# PCIe_x1_edge.net
KiCad netlist of a schematic drawn in Altium Designer
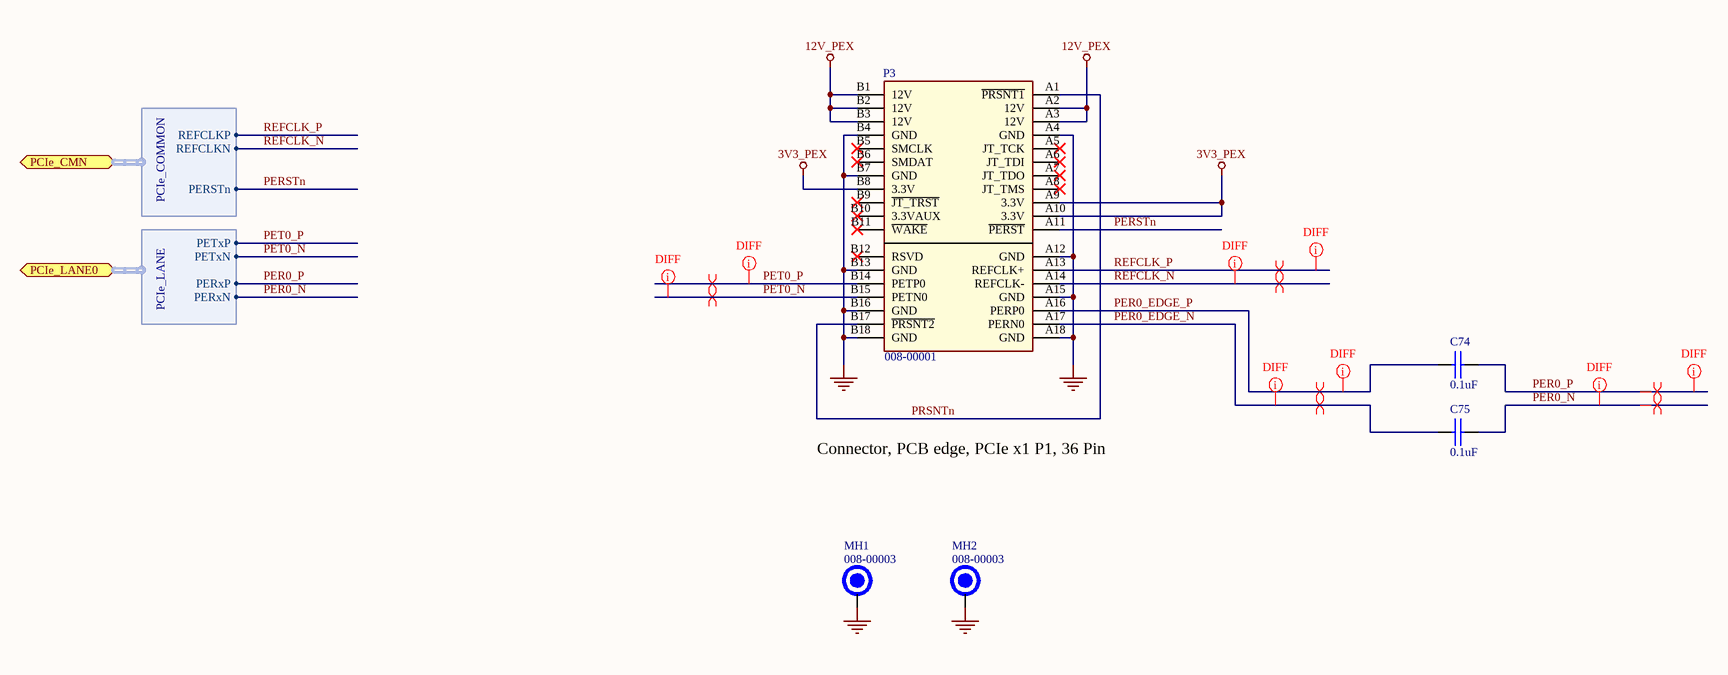
[diagram p0: PCIe_x1_edge.SchDoc]

(export (version "E")
  (design (tool "Eeschema 10.0.6"))
  (components
    (comp (ref "C74")
      (value "0.1uF")
      (footprint "005-00008")
      (description "Capacitor 0.1uF 16V 10% 0402 X7R")
      (fields (field (name "PART NUMBER") "011-00011") (field (name "VOLTAGE") "16V"))
      (libsource (lib "CES Component Library") (part "004-00003"))
    )
    (comp (ref "C75")
      (value "0.1uF")
      (footprint "005-00008")
      (description "Capacitor 0.1uF 16V 10% 0402 X7R")
      (fields (field (name "PART NUMBER") "011-00011") (field (name "VOLTAGE") "16V"))
      (libsource (lib "CES Component Library") (part "004-00003"))
    )
    (comp (ref "MH1")
      (value "004-00017")
      (footprint "005-00019")
      (description "PCB Mounting Hole, Round Pad, 250mil Diameter, 125mil Drill")
      (fields (field (name "PART NUMBER") "008-00003"))
      (libsource (lib "CES Component Library") (part "004-00017"))
    )
    (comp (ref "MH2")
      (value "004-00017")
      (footprint "005-00019")
      (description "PCB Mounting Hole, Round Pad, 250mil Diameter, 125mil Drill")
      (fields (field (name "PART NUMBER") "008-00003"))
      (libsource (lib "CES Component Library") (part "004-00017"))
    )
    (comp (ref "P3")
      (value "004-00018")
      (footprint "005-00020")
      (description "Connector, PCB edge, PCIe x1 P1, 36 Pin")
      (fields (field (name "PART NUMBER") "008-00001"))
      (libsource (lib "CES Component Library") (part "004-00018"))
    )
  )
  (nets
    (net (code "3") (name "/PER0_EDGE_N") (class "Default")
      (node (ref "C75") (pin "1") (pinfunction "1_1") (pintype "passive"))
      (node (ref "P3") (pin "A17") (pinfunction "PERN0_A17") (pintype "passive"))
    )
    (net (code "4") (name "/PER0_EDGE_P") (class "Default")
      (node (ref "C74") (pin "1") (pinfunction "1_1") (pintype "passive"))
      (node (ref "P3") (pin "A16") (pinfunction "PERP0_A16") (pintype "passive"))
    )
    (net (code "5") (name "/PER0_N") (class "Default")
      (node (ref "C75") (pin "2") (pinfunction "2_2") (pintype "passive"))
    )
    (net (code "6") (name "/PER0_P") (class "Default")
      (node (ref "C74") (pin "2") (pinfunction "2_2") (pintype "passive"))
    )
    (net (code "7") (name "/PERSTn") (class "Default")
      (node (ref "P3") (pin "A11") (pinfunction "~{PERST}_A11") (pintype "passive"))
    )
    (net (code "8") (name "/PET0_N") (class "Default")
      (node (ref "P3") (pin "B15") (pinfunction "PETN0_B15") (pintype "passive"))
    )
    (net (code "9") (name "/PET0_P") (class "Default")
      (node (ref "P3") (pin "B14") (pinfunction "PETP0_B14") (pintype "passive"))
    )
    (net (code "10") (name "/PRSNTn") (class "Default")
      (node (ref "P3") (pin "A1") (pinfunction "~{PRSNT1}_A1") (pintype "passive"))
      (node (ref "P3") (pin "B17") (pinfunction "~{PRSNT2}_B17") (pintype "passive"))
    )
    (net (code "11") (name "/REFCLK_N") (class "Default")
      (node (ref "P3") (pin "A14") (pinfunction "REFCLK-_A14") (pintype "passive"))
    )
    (net (code "12") (name "/REFCLK_P") (class "Default")
      (node (ref "P3") (pin "A13") (pinfunction "REFCLK+_A13") (pintype "passive"))
    )
    (net (code "15") (name "3V3_PEX") (class "Default")
      (node (ref "P3") (pin "A10") (pinfunction "3.3V_A10") (pintype "passive"))
      (node (ref "P3") (pin "A9") (pinfunction "3.3V_A9") (pintype "passive"))
      (node (ref "P3") (pin "B8") (pinfunction "3.3V_B8") (pintype "passive"))
    )
    (net (code "16") (name "12V_PEX") (class "Default")
      (node (ref "P3") (pin "A2") (pinfunction "12V_A2") (pintype "passive"))
      (node (ref "P3") (pin "A3") (pinfunction "12V_A3") (pintype "passive"))
      (node (ref "P3") (pin "B1") (pinfunction "12V_B1") (pintype "passive"))
      (node (ref "P3") (pin "B2") (pinfunction "12V_B2") (pintype "passive"))
      (node (ref "P3") (pin "B3") (pinfunction "12V_B3") (pintype "passive"))
    )
    (net (code "17") (name "GND") (class "Default")
      (node (ref "MH1") (pin "1") (pinfunction "1_1") (pintype "passive"))
      (node (ref "MH2") (pin "1") (pinfunction "1_1") (pintype "passive"))
      (node (ref "P3") (pin "A12") (pinfunction "GND_A12") (pintype "passive"))
      (node (ref "P3") (pin "A15") (pinfunction "GND_A15") (pintype "passive"))
      (node (ref "P3") (pin "A18") (pinfunction "GND_A18") (pintype "passive"))
      (node (ref "P3") (pin "A4") (pinfunction "GND_A4") (pintype "passive"))
      (node (ref "P3") (pin "B13") (pinfunction "GND_B13") (pintype "passive"))
      (node (ref "P3") (pin "B16") (pinfunction "GND_B16") (pintype "passive"))
      (node (ref "P3") (pin "B18") (pinfunction "GND_B18") (pintype "passive"))
      (node (ref "P3") (pin "B4") (pinfunction "GND_B4") (pintype "passive"))
      (node (ref "P3") (pin "B7") (pinfunction "GND_B7") (pintype "passive"))
    )
    (net (code "18") (name "unconnected-(P3-3.3VAUX-PadB10)") (class "Default")
      (node (ref "P3") (pin "B10") (pinfunction "3.3VAUX_B10") (pintype "passive+no_connect"))
    )
    (net (code "19") (name "unconnected-(P3-JT_TCK-PadA5)") (class "Default")
      (node (ref "P3") (pin "A5") (pinfunction "JT_TCK_A5") (pintype "passive+no_connect"))
    )
    (net (code "20") (name "unconnected-(P3-JT_TDI-PadA6)") (class "Default")
      (node (ref "P3") (pin "A6") (pinfunction "JT_TDI_A6") (pintype "passive+no_connect"))
    )
    (net (code "21") (name "unconnected-(P3-JT_TDO-PadA7)") (class "Default")
      (node (ref "P3") (pin "A7") (pinfunction "JT_TDO_A7") (pintype "passive+no_connect"))
    )
    (net (code "22") (name "unconnected-(P3-JT_TMS-PadA8)") (class "Default")
      (node (ref "P3") (pin "A8") (pinfunction "JT_TMS_A8") (pintype "passive+no_connect"))
    )
    (net (code "23") (name "unconnected-(P3-RSVD-PadB12)") (class "Default")
      (node (ref "P3") (pin "B12") (pinfunction "RSVD_B12") (pintype "passive+no_connect"))
    )
    (net (code "24") (name "unconnected-(P3-SMCLK-PadB5)") (class "Default")
      (node (ref "P3") (pin "B5") (pinfunction "SMCLK_B5") (pintype "passive+no_connect"))
    )
    (net (code "25") (name "unconnected-(P3-SMDAT-PadB6)") (class "Default")
      (node (ref "P3") (pin "B6") (pinfunction "SMDAT_B6") (pintype "passive+no_connect"))
    )
    (net (code "26") (name "unconnected-(P3-~{JT_TRST}-PadB9)") (class "Default")
      (node (ref "P3") (pin "B9") (pinfunction "~{JT_TRST}_B9") (pintype "passive+no_connect"))
    )
    (net (code "27") (name "unconnected-(P3-~{WAKE}-PadB11)") (class "Default")
      (node (ref "P3") (pin "B11") (pinfunction "~{WAKE}_B11") (pintype "passive+no_connect"))
    )
  )
)
